# TCRT5000.net
KiCad netlist of a schematic drawn in Altium Designer
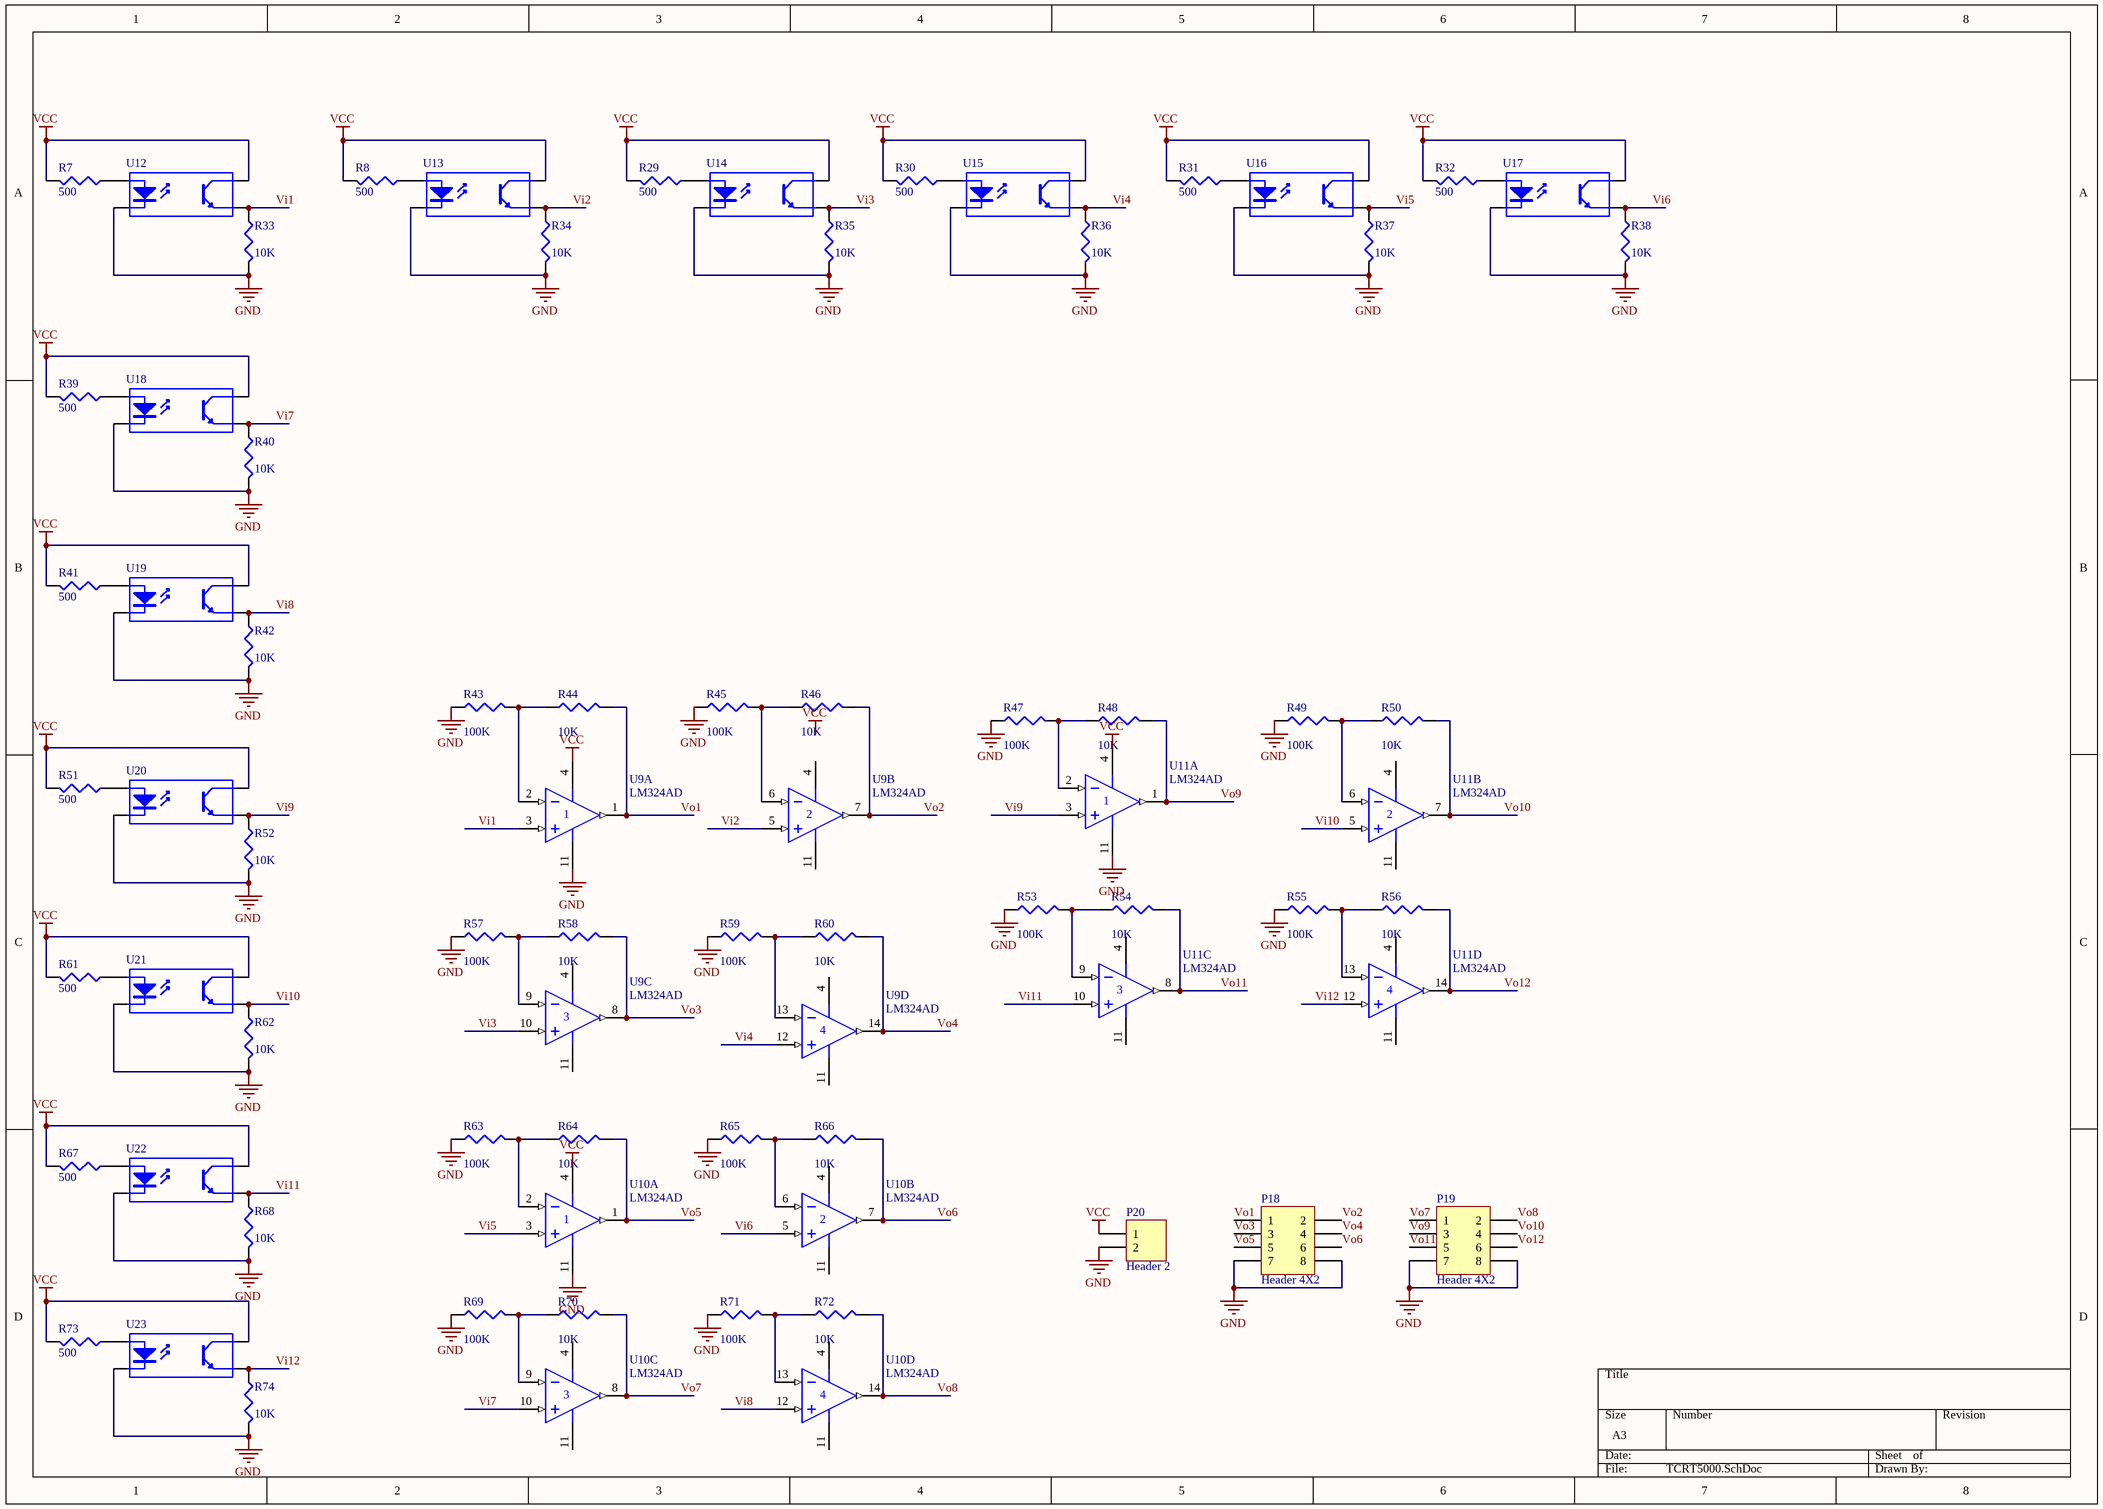
[diagram p0: TCRT5000.SchDoc]

(export (version "E")
  (design (tool "Eeschema 10.0.6"))
  (components
    (comp (ref "P18")
      (value "Header 4X2")
      (footprint "HDR2X4")
      (description "Header, 4-Pin, Dual row")
      (fields (field (name "PUBLISHER") "Altium Limited"))
      (libsource (lib "Miscellaneous Connectors") (part "Header 4X2"))
    )
    (comp (ref "P19")
      (value "Header 4X2")
      (footprint "HDR2X4")
      (description "Header, 4-Pin, Dual row")
      (fields (field (name "PUBLISHER") "Altium Limited"))
      (libsource (lib "Miscellaneous Connectors") (part "Header 4X2"))
    )
    (comp (ref "P20")
      (value "Header 2")
      (footprint "HDR1X2")
      (description "Header, 2-Pin")
      (fields (field (name "PUBLISHER") "Altium Limited"))
      (libsource (lib "Miscellaneous Connectors") (part "Header 2"))
    )
    (comp (ref "R7")
      (value "500")
      (description "Resistor")
      (fields (field (name "Comment") "Res3") (field (name "PUBLISHER") "Altium Limited"))
      (libsource (lib "Miscellaneous Devices") (part "Res3"))
    )
    (comp (ref "R8")
      (value "500")
      (description "Resistor")
      (fields (field (name "Comment") "Res3") (field (name "PUBLISHER") "Altium Limited"))
      (libsource (lib "Miscellaneous Devices") (part "Res3"))
    )
    (comp (ref "R29")
      (value "500")
      (description "Resistor")
      (fields (field (name "Comment") "Res3") (field (name "PUBLISHER") "Altium Limited"))
      (libsource (lib "Miscellaneous Devices") (part "Res3"))
    )
    (comp (ref "R30")
      (value "500")
      (description "Resistor")
      (fields (field (name "Comment") "Res3") (field (name "PUBLISHER") "Altium Limited"))
      (libsource (lib "Miscellaneous Devices") (part "Res3"))
    )
    (comp (ref "R31")
      (value "500")
      (description "Resistor")
      (fields (field (name "Comment") "Res3") (field (name "PUBLISHER") "Altium Limited"))
      (libsource (lib "Miscellaneous Devices") (part "Res3"))
    )
    (comp (ref "R32")
      (value "500")
      (description "Resistor")
      (fields (field (name "Comment") "Res3") (field (name "PUBLISHER") "Altium Limited"))
      (libsource (lib "Miscellaneous Devices") (part "Res3"))
    )
    (comp (ref "R33")
      (value "10K")
      (description "Resistor")
      (fields (field (name "Comment") "Res3") (field (name "PUBLISHER") "Altium Limited"))
      (libsource (lib "Miscellaneous Devices") (part "Res3"))
    )
    (comp (ref "R34")
      (value "10K")
      (description "Resistor")
      (fields (field (name "Comment") "Res3") (field (name "PUBLISHER") "Altium Limited"))
      (libsource (lib "Miscellaneous Devices") (part "Res3"))
    )
    (comp (ref "R35")
      (value "10K")
      (description "Resistor")
      (fields (field (name "Comment") "Res3") (field (name "PUBLISHER") "Altium Limited"))
      (libsource (lib "Miscellaneous Devices") (part "Res3"))
    )
    (comp (ref "R36")
      (value "10K")
      (description "Resistor")
      (fields (field (name "Comment") "Res3") (field (name "PUBLISHER") "Altium Limited"))
      (libsource (lib "Miscellaneous Devices") (part "Res3"))
    )
    (comp (ref "R37")
      (value "10K")
      (description "Resistor")
      (fields (field (name "Comment") "Res3") (field (name "PUBLISHER") "Altium Limited"))
      (libsource (lib "Miscellaneous Devices") (part "Res3"))
    )
    (comp (ref "R38")
      (value "10K")
      (description "Resistor")
      (fields (field (name "Comment") "Res3") (field (name "PUBLISHER") "Altium Limited"))
      (libsource (lib "Miscellaneous Devices") (part "Res3"))
    )
    (comp (ref "R39")
      (value "500")
      (description "Resistor")
      (fields (field (name "Comment") "Res3") (field (name "PUBLISHER") "Altium Limited"))
      (libsource (lib "Miscellaneous Devices") (part "Res3"))
    )
    (comp (ref "R40")
      (value "10K")
      (description "Resistor")
      (fields (field (name "Comment") "Res3") (field (name "PUBLISHER") "Altium Limited"))
      (libsource (lib "Miscellaneous Devices") (part "Res3"))
    )
    (comp (ref "R41")
      (value "500")
      (description "Resistor")
      (fields (field (name "Comment") "Res3") (field (name "PUBLISHER") "Altium Limited"))
      (libsource (lib "Miscellaneous Devices") (part "Res3"))
    )
    (comp (ref "R42")
      (value "10K")
      (description "Resistor")
      (fields (field (name "Comment") "Res3") (field (name "PUBLISHER") "Altium Limited"))
      (libsource (lib "Miscellaneous Devices") (part "Res3"))
    )
    (comp (ref "R43")
      (value "100K")
      (description "Resistor")
      (fields (field (name "Comment") "Res3") (field (name "PUBLISHER") "Altium Limited"))
      (libsource (lib "Miscellaneous Devices") (part "Res3"))
    )
    (comp (ref "R44")
      (value "10K")
      (description "Resistor")
      (fields (field (name "Comment") "Res3") (field (name "PUBLISHER") "Altium Limited"))
      (libsource (lib "Miscellaneous Devices") (part "Res3"))
    )
    (comp (ref "R45")
      (value "100K")
      (description "Resistor")
      (fields (field (name "Comment") "Res3") (field (name "PUBLISHER") "Altium Limited"))
      (libsource (lib "Miscellaneous Devices") (part "Res3"))
    )
    (comp (ref "R46")
      (value "10K")
      (description "Resistor")
      (fields (field (name "Comment") "Res3") (field (name "PUBLISHER") "Altium Limited"))
      (libsource (lib "Miscellaneous Devices") (part "Res3"))
    )
    (comp (ref "R47")
      (value "100K")
      (description "Resistor")
      (fields (field (name "Comment") "Res3") (field (name "PUBLISHER") "Altium Limited"))
      (libsource (lib "Miscellaneous Devices") (part "Res3"))
    )
    (comp (ref "R48")
      (value "10K")
      (description "Resistor")
      (fields (field (name "Comment") "Res3") (field (name "PUBLISHER") "Altium Limited"))
      (libsource (lib "Miscellaneous Devices") (part "Res3"))
    )
    (comp (ref "R49")
      (value "100K")
      (description "Resistor")
      (fields (field (name "Comment") "Res3") (field (name "PUBLISHER") "Altium Limited"))
      (libsource (lib "Miscellaneous Devices") (part "Res3"))
    )
    (comp (ref "R50")
      (value "10K")
      (description "Resistor")
      (fields (field (name "Comment") "Res3") (field (name "PUBLISHER") "Altium Limited"))
      (libsource (lib "Miscellaneous Devices") (part "Res3"))
    )
    (comp (ref "R51")
      (value "500")
      (description "Resistor")
      (fields (field (name "Comment") "Res3") (field (name "PUBLISHER") "Altium Limited"))
      (libsource (lib "Miscellaneous Devices") (part "Res3"))
    )
    (comp (ref "R52")
      (value "10K")
      (description "Resistor")
      (fields (field (name "Comment") "Res3") (field (name "PUBLISHER") "Altium Limited"))
      (libsource (lib "Miscellaneous Devices") (part "Res3"))
    )
    (comp (ref "R53")
      (value "100K")
      (description "Resistor")
      (fields (field (name "Comment") "Res3") (field (name "PUBLISHER") "Altium Limited"))
      (libsource (lib "Miscellaneous Devices") (part "Res3"))
    )
    (comp (ref "R54")
      (value "10K")
      (description "Resistor")
      (fields (field (name "Comment") "Res3") (field (name "PUBLISHER") "Altium Limited"))
      (libsource (lib "Miscellaneous Devices") (part "Res3"))
    )
    (comp (ref "R55")
      (value "100K")
      (description "Resistor")
      (fields (field (name "Comment") "Res3") (field (name "PUBLISHER") "Altium Limited"))
      (libsource (lib "Miscellaneous Devices") (part "Res3"))
    )
    (comp (ref "R56")
      (value "10K")
      (description "Resistor")
      (fields (field (name "Comment") "Res3") (field (name "PUBLISHER") "Altium Limited"))
      (libsource (lib "Miscellaneous Devices") (part "Res3"))
    )
    (comp (ref "R57")
      (value "100K")
      (description "Resistor")
      (fields (field (name "Comment") "Res3") (field (name "PUBLISHER") "Altium Limited"))
      (libsource (lib "Miscellaneous Devices") (part "Res3"))
    )
    (comp (ref "R58")
      (value "10K")
      (description "Resistor")
      (fields (field (name "Comment") "Res3") (field (name "PUBLISHER") "Altium Limited"))
      (libsource (lib "Miscellaneous Devices") (part "Res3"))
    )
    (comp (ref "R59")
      (value "100K")
      (description "Resistor")
      (fields (field (name "Comment") "Res3") (field (name "PUBLISHER") "Altium Limited"))
      (libsource (lib "Miscellaneous Devices") (part "Res3"))
    )
    (comp (ref "R60")
      (value "10K")
      (description "Resistor")
      (fields (field (name "Comment") "Res3") (field (name "PUBLISHER") "Altium Limited"))
      (libsource (lib "Miscellaneous Devices") (part "Res3"))
    )
    (comp (ref "R61")
      (value "500")
      (description "Resistor")
      (fields (field (name "Comment") "Res3") (field (name "PUBLISHER") "Altium Limited"))
      (libsource (lib "Miscellaneous Devices") (part "Res3"))
    )
    (comp (ref "R62")
      (value "10K")
      (description "Resistor")
      (fields (field (name "Comment") "Res3") (field (name "PUBLISHER") "Altium Limited"))
      (libsource (lib "Miscellaneous Devices") (part "Res3"))
    )
    (comp (ref "R63")
      (value "100K")
      (description "Resistor")
      (fields (field (name "Comment") "Res3") (field (name "PUBLISHER") "Altium Limited"))
      (libsource (lib "Miscellaneous Devices") (part "Res3"))
    )
    (comp (ref "R64")
      (value "10K")
      (description "Resistor")
      (fields (field (name "Comment") "Res3") (field (name "PUBLISHER") "Altium Limited"))
      (libsource (lib "Miscellaneous Devices") (part "Res3"))
    )
    (comp (ref "R65")
      (value "100K")
      (description "Resistor")
      (fields (field (name "Comment") "Res3") (field (name "PUBLISHER") "Altium Limited"))
      (libsource (lib "Miscellaneous Devices") (part "Res3"))
    )
    (comp (ref "R66")
      (value "10K")
      (description "Resistor")
      (fields (field (name "Comment") "Res3") (field (name "PUBLISHER") "Altium Limited"))
      (libsource (lib "Miscellaneous Devices") (part "Res3"))
    )
    (comp (ref "R67")
      (value "500")
      (description "Resistor")
      (fields (field (name "Comment") "Res3") (field (name "PUBLISHER") "Altium Limited"))
      (libsource (lib "Miscellaneous Devices") (part "Res3"))
    )
    (comp (ref "R68")
      (value "10K")
      (description "Resistor")
      (fields (field (name "Comment") "Res3") (field (name "PUBLISHER") "Altium Limited"))
      (libsource (lib "Miscellaneous Devices") (part "Res3"))
    )
    (comp (ref "R69")
      (value "100K")
      (description "Resistor")
      (fields (field (name "Comment") "Res3") (field (name "PUBLISHER") "Altium Limited"))
      (libsource (lib "Miscellaneous Devices") (part "Res3"))
    )
    (comp (ref "R70")
      (value "10K")
      (description "Resistor")
      (fields (field (name "Comment") "Res3") (field (name "PUBLISHER") "Altium Limited"))
      (libsource (lib "Miscellaneous Devices") (part "Res3"))
    )
    (comp (ref "R71")
      (value "100K")
      (description "Resistor")
      (fields (field (name "Comment") "Res3") (field (name "PUBLISHER") "Altium Limited"))
      (libsource (lib "Miscellaneous Devices") (part "Res3"))
    )
    (comp (ref "R72")
      (value "10K")
      (description "Resistor")
      (fields (field (name "Comment") "Res3") (field (name "PUBLISHER") "Altium Limited"))
      (libsource (lib "Miscellaneous Devices") (part "Res3"))
    )
    (comp (ref "R73")
      (value "500")
      (description "Resistor")
      (fields (field (name "Comment") "Res3") (field (name "PUBLISHER") "Altium Limited"))
      (libsource (lib "Miscellaneous Devices") (part "Res3"))
    )
    (comp (ref "R74")
      (value "10K")
      (description "Resistor")
      (fields (field (name "Comment") "Res3") (field (name "PUBLISHER") "Altium Limited"))
      (libsource (lib "Miscellaneous Devices") (part "Res3"))
    )
    (comp (ref "U9")
      (value "LM324AD")
      (footprint "D014_N")
      (description "Quadruple Operational Amplifier")
      (fields (field (name "PUBLISHER") "Altium Limited"))
      (libsource (lib "TI Operational Amplifier") (part "LM324AD"))
    )
    (comp (ref "U10")
      (value "LM324AD")
      (footprint "D014_N")
      (description "Quadruple Operational Amplifier")
      (fields (field (name "PUBLISHER") "Altium Limited"))
      (libsource (lib "TI Operational Amplifier") (part "LM324AD"))
    )
    (comp (ref "U11")
      (value "LM324AD")
      (footprint "D014_N")
      (description "Quadruple Operational Amplifier")
      (fields (field (name "PUBLISHER") "Altium Limited"))
      (libsource (lib "TI Operational Amplifier") (part "LM324AD"))
    )
    (comp (ref "U12")
      (value "Optoisolator1")
      (footprint "TCRT5000")
      (description "4-Pin Phototransistor Optocoupler")
      (fields (field (name "PUBLISHER") "Altium Limited"))
      (libsource (lib "Miscellaneous Devices") (part "Optoisolator1"))
    )
    (comp (ref "U13")
      (value "Optoisolator1")
      (footprint "TCRT5000")
      (description "4-Pin Phototransistor Optocoupler")
      (fields (field (name "PUBLISHER") "Altium Limited"))
      (libsource (lib "Miscellaneous Devices") (part "Optoisolator1"))
    )
    (comp (ref "U14")
      (value "Optoisolator1")
      (footprint "TCRT5000")
      (description "4-Pin Phototransistor Optocoupler")
      (fields (field (name "PUBLISHER") "Altium Limited"))
      (libsource (lib "Miscellaneous Devices") (part "Optoisolator1"))
    )
    (comp (ref "U15")
      (value "Optoisolator1")
      (footprint "TCRT5000")
      (description "4-Pin Phototransistor Optocoupler")
      (fields (field (name "PUBLISHER") "Altium Limited"))
      (libsource (lib "Miscellaneous Devices") (part "Optoisolator1"))
    )
    (comp (ref "U16")
      (value "Optoisolator1")
      (footprint "TCRT5000")
      (description "4-Pin Phototransistor Optocoupler")
      (fields (field (name "PUBLISHER") "Altium Limited"))
      (libsource (lib "Miscellaneous Devices") (part "Optoisolator1"))
    )
    (comp (ref "U17")
      (value "Optoisolator1")
      (footprint "TCRT5000")
      (description "4-Pin Phototransistor Optocoupler")
      (fields (field (name "PUBLISHER") "Altium Limited"))
      (libsource (lib "Miscellaneous Devices") (part "Optoisolator1"))
    )
    (comp (ref "U18")
      (value "Optoisolator1")
      (footprint "TCRT5000")
      (description "4-Pin Phototransistor Optocoupler")
      (fields (field (name "PUBLISHER") "Altium Limited"))
      (libsource (lib "Miscellaneous Devices") (part "Optoisolator1"))
    )
    (comp (ref "U19")
      (value "Optoisolator1")
      (footprint "TCRT5000")
      (description "4-Pin Phototransistor Optocoupler")
      (fields (field (name "PUBLISHER") "Altium Limited"))
      (libsource (lib "Miscellaneous Devices") (part "Optoisolator1"))
    )
    (comp (ref "U20")
      (value "Optoisolator1")
      (footprint "TCRT5000")
      (description "4-Pin Phototransistor Optocoupler")
      (fields (field (name "PUBLISHER") "Altium Limited"))
      (libsource (lib "Miscellaneous Devices") (part "Optoisolator1"))
    )
    (comp (ref "U21")
      (value "Optoisolator1")
      (footprint "TCRT5000")
      (description "4-Pin Phototransistor Optocoupler")
      (fields (field (name "PUBLISHER") "Altium Limited"))
      (libsource (lib "Miscellaneous Devices") (part "Optoisolator1"))
    )
    (comp (ref "U22")
      (value "Optoisolator1")
      (footprint "TCRT5000")
      (description "4-Pin Phototransistor Optocoupler")
      (fields (field (name "PUBLISHER") "Altium Limited"))
      (libsource (lib "Miscellaneous Devices") (part "Optoisolator1"))
    )
    (comp (ref "U23")
      (value "Optoisolator1")
      (footprint "TCRT5000")
      (description "4-Pin Phototransistor Optocoupler")
      (fields (field (name "PUBLISHER") "Altium Limited"))
      (libsource (lib "Miscellaneous Devices") (part "Optoisolator1"))
    )
  )
  (nets
    (net (code "1") (name "/Vi1") (class "Default")
      (node (ref "R33") (pin "1") (pinfunction "1_1") (pintype "passive"))
      (node (ref "U12") (pin "3") (pinfunction "E_3") (pintype "passive"))
      (node (ref "U9") (pin "3") (pinfunction "IN+_3") (pintype "input"))
    )
    (net (code "2") (name "/Vi2") (class "Default")
      (node (ref "R34") (pin "1") (pinfunction "1_1") (pintype "passive"))
      (node (ref "U13") (pin "3") (pinfunction "E_3") (pintype "passive"))
      (node (ref "U9") (pin "5") (pinfunction "IN+_5") (pintype "input"))
    )
    (net (code "3") (name "/Vi3") (class "Default")
      (node (ref "R35") (pin "1") (pinfunction "1_1") (pintype "passive"))
      (node (ref "U14") (pin "3") (pinfunction "E_3") (pintype "passive"))
      (node (ref "U9") (pin "10") (pinfunction "IN+_10") (pintype "input"))
    )
    (net (code "4") (name "/Vi4") (class "Default")
      (node (ref "R36") (pin "1") (pinfunction "1_1") (pintype "passive"))
      (node (ref "U15") (pin "3") (pinfunction "E_3") (pintype "passive"))
      (node (ref "U9") (pin "12") (pinfunction "IN+_12") (pintype "input"))
    )
    (net (code "5") (name "/Vi5") (class "Default")
      (node (ref "R37") (pin "1") (pinfunction "1_1") (pintype "passive"))
      (node (ref "U10") (pin "3") (pinfunction "IN+_3") (pintype "input"))
      (node (ref "U16") (pin "3") (pinfunction "E_3") (pintype "passive"))
    )
    (net (code "6") (name "/Vi6") (class "Default")
      (node (ref "R38") (pin "1") (pinfunction "1_1") (pintype "passive"))
      (node (ref "U10") (pin "5") (pinfunction "IN+_5") (pintype "input"))
      (node (ref "U17") (pin "3") (pinfunction "E_3") (pintype "passive"))
    )
    (net (code "7") (name "/Vi7") (class "Default")
      (node (ref "R40") (pin "1") (pinfunction "1_1") (pintype "passive"))
      (node (ref "U10") (pin "10") (pinfunction "IN+_10") (pintype "input"))
      (node (ref "U18") (pin "3") (pinfunction "E_3") (pintype "passive"))
    )
    (net (code "8") (name "/Vi8") (class "Default")
      (node (ref "R42") (pin "1") (pinfunction "1_1") (pintype "passive"))
      (node (ref "U10") (pin "12") (pinfunction "IN+_12") (pintype "input"))
      (node (ref "U19") (pin "3") (pinfunction "E_3") (pintype "passive"))
    )
    (net (code "9") (name "/Vi9") (class "Default")
      (node (ref "R52") (pin "1") (pinfunction "1_1") (pintype "passive"))
      (node (ref "U11") (pin "3") (pinfunction "IN+_3") (pintype "input"))
      (node (ref "U20") (pin "3") (pinfunction "E_3") (pintype "passive"))
    )
    (net (code "10") (name "/Vi10") (class "Default")
      (node (ref "R62") (pin "1") (pinfunction "1_1") (pintype "passive"))
      (node (ref "U11") (pin "5") (pinfunction "IN+_5") (pintype "input"))
      (node (ref "U21") (pin "3") (pinfunction "E_3") (pintype "passive"))
    )
    (net (code "11") (name "/Vi11") (class "Default")
      (node (ref "R68") (pin "1") (pinfunction "1_1") (pintype "passive"))
      (node (ref "U11") (pin "10") (pinfunction "IN+_10") (pintype "input"))
      (node (ref "U22") (pin "3") (pinfunction "E_3") (pintype "passive"))
    )
    (net (code "12") (name "/Vi12") (class "Default")
      (node (ref "R74") (pin "1") (pinfunction "1_1") (pintype "passive"))
      (node (ref "U11") (pin "12") (pinfunction "IN+_12") (pintype "input"))
      (node (ref "U23") (pin "3") (pinfunction "E_3") (pintype "passive"))
    )
    (net (code "13") (name "/Vo1") (class "Default")
      (node (ref "P18") (pin "1") (pinfunction "1_1") (pintype "passive"))
      (node (ref "R44") (pin "2") (pinfunction "2_2") (pintype "passive"))
      (node (ref "U9") (pin "1") (pinfunction "OUT_1") (pintype "output"))
    )
    (net (code "14") (name "/Vo2") (class "Default")
      (node (ref "P18") (pin "2") (pinfunction "2_2") (pintype "passive"))
      (node (ref "R46") (pin "2") (pinfunction "2_2") (pintype "passive"))
      (node (ref "U9") (pin "7") (pinfunction "OUT_7") (pintype "output"))
    )
    (net (code "15") (name "/Vo3") (class "Default")
      (node (ref "P18") (pin "3") (pinfunction "3_3") (pintype "passive"))
      (node (ref "R58") (pin "2") (pinfunction "2_2") (pintype "passive"))
      (node (ref "U9") (pin "8") (pinfunction "OUT_8") (pintype "output"))
    )
    (net (code "16") (name "/Vo4") (class "Default")
      (node (ref "P18") (pin "4") (pinfunction "4_4") (pintype "passive"))
      (node (ref "R60") (pin "2") (pinfunction "2_2") (pintype "passive"))
      (node (ref "U9") (pin "14") (pinfunction "OUT_14") (pintype "output"))
    )
    (net (code "17") (name "/Vo5") (class "Default")
      (node (ref "P18") (pin "5") (pinfunction "5_5") (pintype "passive"))
      (node (ref "R64") (pin "2") (pinfunction "2_2") (pintype "passive"))
      (node (ref "U10") (pin "1") (pinfunction "OUT_1") (pintype "output"))
    )
    (net (code "18") (name "/Vo6") (class "Default")
      (node (ref "P18") (pin "6") (pinfunction "6_6") (pintype "passive"))
      (node (ref "R66") (pin "2") (pinfunction "2_2") (pintype "passive"))
      (node (ref "U10") (pin "7") (pinfunction "OUT_7") (pintype "output"))
    )
    (net (code "19") (name "/Vo7") (class "Default")
      (node (ref "P19") (pin "1") (pinfunction "1_1") (pintype "passive"))
      (node (ref "R70") (pin "2") (pinfunction "2_2") (pintype "passive"))
      (node (ref "U10") (pin "8") (pinfunction "OUT_8") (pintype "output"))
    )
    (net (code "20") (name "/Vo8") (class "Default")
      (node (ref "P19") (pin "2") (pinfunction "2_2") (pintype "passive"))
      (node (ref "R72") (pin "2") (pinfunction "2_2") (pintype "passive"))
      (node (ref "U10") (pin "14") (pinfunction "OUT_14") (pintype "output"))
    )
    (net (code "21") (name "/Vo9") (class "Default")
      (node (ref "P19") (pin "3") (pinfunction "3_3") (pintype "passive"))
      (node (ref "R48") (pin "2") (pinfunction "2_2") (pintype "passive"))
      (node (ref "U11") (pin "1") (pinfunction "OUT_1") (pintype "output"))
    )
    (net (code "22") (name "/Vo10") (class "Default")
      (node (ref "P19") (pin "4") (pinfunction "4_4") (pintype "passive"))
      (node (ref "R50") (pin "2") (pinfunction "2_2") (pintype "passive"))
      (node (ref "U11") (pin "7") (pinfunction "OUT_7") (pintype "output"))
    )
    (net (code "23") (name "/Vo11") (class "Default")
      (node (ref "P19") (pin "5") (pinfunction "5_5") (pintype "passive"))
      (node (ref "R54") (pin "2") (pinfunction "2_2") (pintype "passive"))
      (node (ref "U11") (pin "8") (pinfunction "OUT_8") (pintype "output"))
    )
    (net (code "24") (name "/Vo12") (class "Default")
      (node (ref "P19") (pin "6") (pinfunction "6_6") (pintype "passive"))
      (node (ref "R56") (pin "2") (pinfunction "2_2") (pintype "passive"))
      (node (ref "U11") (pin "14") (pinfunction "OUT_14") (pintype "output"))
    )
    (net (code "25") (name "GND") (class "Default")
      (node (ref "P18") (pin "7") (pinfunction "7_7") (pintype "passive"))
      (node (ref "P18") (pin "8") (pinfunction "8_8") (pintype "passive"))
      (node (ref "P19") (pin "7") (pinfunction "7_7") (pintype "passive"))
      (node (ref "P19") (pin "8") (pinfunction "8_8") (pintype "passive"))
      (node (ref "P20") (pin "2") (pinfunction "2_2") (pintype "passive"))
      (node (ref "R33") (pin "2") (pinfunction "2_2") (pintype "passive"))
      (node (ref "R34") (pin "2") (pinfunction "2_2") (pintype "passive"))
      (node (ref "R35") (pin "2") (pinfunction "2_2") (pintype "passive"))
      (node (ref "R36") (pin "2") (pinfunction "2_2") (pintype "passive"))
      (node (ref "R37") (pin "2") (pinfunction "2_2") (pintype "passive"))
      (node (ref "R38") (pin "2") (pinfunction "2_2") (pintype "passive"))
      (node (ref "R40") (pin "2") (pinfunction "2_2") (pintype "passive"))
      (node (ref "R42") (pin "2") (pinfunction "2_2") (pintype "passive"))
      (node (ref "R43") (pin "1") (pinfunction "1_1") (pintype "passive"))
      (node (ref "R45") (pin "1") (pinfunction "1_1") (pintype "passive"))
      (node (ref "R47") (pin "1") (pinfunction "1_1") (pintype "passive"))
      (node (ref "R49") (pin "1") (pinfunction "1_1") (pintype "passive"))
      (node (ref "R52") (pin "2") (pinfunction "2_2") (pintype "passive"))
      (node (ref "R53") (pin "1") (pinfunction "1_1") (pintype "passive"))
      (node (ref "R55") (pin "1") (pinfunction "1_1") (pintype "passive"))
      (node (ref "R57") (pin "1") (pinfunction "1_1") (pintype "passive"))
      (node (ref "R59") (pin "1") (pinfunction "1_1") (pintype "passive"))
      (node (ref "R62") (pin "2") (pinfunction "2_2") (pintype "passive"))
      (node (ref "R63") (pin "1") (pinfunction "1_1") (pintype "passive"))
      (node (ref "R65") (pin "1") (pinfunction "1_1") (pintype "passive"))
      (node (ref "R68") (pin "2") (pinfunction "2_2") (pintype "passive"))
      (node (ref "R69") (pin "1") (pinfunction "1_1") (pintype "passive"))
      (node (ref "R71") (pin "1") (pinfunction "1_1") (pintype "passive"))
      (node (ref "R74") (pin "2") (pinfunction "2_2") (pintype "passive"))
      (node (ref "U10") (pin "11") (pinfunction "V-_11") (pintype "power_in"))
      (node (ref "U11") (pin "11") (pinfunction "V-_11") (pintype "power_in"))
      (node (ref "U12") (pin "2") (pinfunction "K_2") (pintype "passive"))
      (node (ref "U13") (pin "2") (pinfunction "K_2") (pintype "passive"))
      (node (ref "U14") (pin "2") (pinfunction "K_2") (pintype "passive"))
      (node (ref "U15") (pin "2") (pinfunction "K_2") (pintype "passive"))
      (node (ref "U16") (pin "2") (pinfunction "K_2") (pintype "passive"))
      (node (ref "U17") (pin "2") (pinfunction "K_2") (pintype "passive"))
      (node (ref "U18") (pin "2") (pinfunction "K_2") (pintype "passive"))
      (node (ref "U19") (pin "2") (pinfunction "K_2") (pintype "passive"))
      (node (ref "U20") (pin "2") (pinfunction "K_2") (pintype "passive"))
      (node (ref "U21") (pin "2") (pinfunction "K_2") (pintype "passive"))
      (node (ref "U22") (pin "2") (pinfunction "K_2") (pintype "passive"))
      (node (ref "U23") (pin "2") (pinfunction "K_2") (pintype "passive"))
      (node (ref "U9") (pin "11") (pinfunction "V-_11") (pintype "power_in"))
    )
    (net (code "26") (name "Net-(U9A-IN-)") (class "Default")
      (node (ref "R43") (pin "2") (pinfunction "2_2") (pintype "passive"))
      (node (ref "R44") (pin "1") (pinfunction "1_1") (pintype "passive"))
      (node (ref "U9") (pin "2") (pinfunction "IN-_2") (pintype "input"))
    )
    (net (code "27") (name "Net-(U9B-IN-)") (class "Default")
      (node (ref "R45") (pin "2") (pinfunction "2_2") (pintype "passive"))
      (node (ref "R46") (pin "1") (pinfunction "1_1") (pintype "passive"))
      (node (ref "U9") (pin "6") (pinfunction "IN-_6") (pintype "input"))
    )
    (net (code "28") (name "Net-(U9C-IN-)") (class "Default")
      (node (ref "R57") (pin "2") (pinfunction "2_2") (pintype "passive"))
      (node (ref "R58") (pin "1") (pinfunction "1_1") (pintype "passive"))
      (node (ref "U9") (pin "9") (pinfunction "IN-_9") (pintype "input"))
    )
    (net (code "29") (name "Net-(U9D-IN-)") (class "Default")
      (node (ref "R59") (pin "2") (pinfunction "2_2") (pintype "passive"))
      (node (ref "R60") (pin "1") (pinfunction "1_1") (pintype "passive"))
      (node (ref "U9") (pin "13") (pinfunction "IN-_13") (pintype "input"))
    )
    (net (code "30") (name "Net-(U10A-IN-)") (class "Default")
      (node (ref "R63") (pin "2") (pinfunction "2_2") (pintype "passive"))
      (node (ref "R64") (pin "1") (pinfunction "1_1") (pintype "passive"))
      (node (ref "U10") (pin "2") (pinfunction "IN-_2") (pintype "input"))
    )
    (net (code "31") (name "Net-(U10B-IN-)") (class "Default")
      (node (ref "R65") (pin "2") (pinfunction "2_2") (pintype "passive"))
      (node (ref "R66") (pin "1") (pinfunction "1_1") (pintype "passive"))
      (node (ref "U10") (pin "6") (pinfunction "IN-_6") (pintype "input"))
    )
    (net (code "32") (name "Net-(U10C-IN-)") (class "Default")
      (node (ref "R69") (pin "2") (pinfunction "2_2") (pintype "passive"))
      (node (ref "R70") (pin "1") (pinfunction "1_1") (pintype "passive"))
      (node (ref "U10") (pin "9") (pinfunction "IN-_9") (pintype "input"))
    )
    (net (code "33") (name "Net-(U10D-IN-)") (class "Default")
      (node (ref "R71") (pin "2") (pinfunction "2_2") (pintype "passive"))
      (node (ref "R72") (pin "1") (pinfunction "1_1") (pintype "passive"))
      (node (ref "U10") (pin "13") (pinfunction "IN-_13") (pintype "input"))
    )
    (net (code "34") (name "Net-(U11A-IN-)") (class "Default")
      (node (ref "R47") (pin "2") (pinfunction "2_2") (pintype "passive"))
      (node (ref "R48") (pin "1") (pinfunction "1_1") (pintype "passive"))
      (node (ref "U11") (pin "2") (pinfunction "IN-_2") (pintype "input"))
    )
    (net (code "35") (name "Net-(U11B-IN-)") (class "Default")
      (node (ref "R49") (pin "2") (pinfunction "2_2") (pintype "passive"))
      (node (ref "R50") (pin "1") (pinfunction "1_1") (pintype "passive"))
      (node (ref "U11") (pin "6") (pinfunction "IN-_6") (pintype "input"))
    )
    (net (code "36") (name "Net-(U11C-IN-)") (class "Default")
      (node (ref "R53") (pin "2") (pinfunction "2_2") (pintype "passive"))
      (node (ref "R54") (pin "1") (pinfunction "1_1") (pintype "passive"))
      (node (ref "U11") (pin "9") (pinfunction "IN-_9") (pintype "input"))
    )
    (net (code "37") (name "Net-(U11D-IN-)") (class "Default")
      (node (ref "R55") (pin "2") (pinfunction "2_2") (pintype "passive"))
      (node (ref "R56") (pin "1") (pinfunction "1_1") (pintype "passive"))
      (node (ref "U11") (pin "13") (pinfunction "IN-_13") (pintype "input"))
    )
    (net (code "38") (name "Net-(U12-A)") (class "Default")
      (node (ref "R7") (pin "1") (pinfunction "1_1") (pintype "passive"))
      (node (ref "U12") (pin "1") (pinfunction "A_1") (pintype "passive"))
    )
    (net (code "39") (name "Net-(U13-A)") (class "Default")
      (node (ref "R8") (pin "1") (pinfunction "1_1") (pintype "passive"))
      (node (ref "U13") (pin "1") (pinfunction "A_1") (pintype "passive"))
    )
    (net (code "40") (name "Net-(U14-A)") (class "Default")
      (node (ref "R29") (pin "1") (pinfunction "1_1") (pintype "passive"))
      (node (ref "U14") (pin "1") (pinfunction "A_1") (pintype "passive"))
    )
    (net (code "41") (name "Net-(U15-A)") (class "Default")
      (node (ref "R30") (pin "1") (pinfunction "1_1") (pintype "passive"))
      (node (ref "U15") (pin "1") (pinfunction "A_1") (pintype "passive"))
    )
    (net (code "42") (name "Net-(U16-A)") (class "Default")
      (node (ref "R31") (pin "1") (pinfunction "1_1") (pintype "passive"))
      (node (ref "U16") (pin "1") (pinfunction "A_1") (pintype "passive"))
    )
    (net (code "43") (name "Net-(U17-A)") (class "Default")
      (node (ref "R32") (pin "1") (pinfunction "1_1") (pintype "passive"))
      (node (ref "U17") (pin "1") (pinfunction "A_1") (pintype "passive"))
    )
    (net (code "44") (name "Net-(U18-A)") (class "Default")
      (node (ref "R39") (pin "1") (pinfunction "1_1") (pintype "passive"))
      (node (ref "U18") (pin "1") (pinfunction "A_1") (pintype "passive"))
    )
    (net (code "45") (name "Net-(U19-A)") (class "Default")
      (node (ref "R41") (pin "1") (pinfunction "1_1") (pintype "passive"))
      (node (ref "U19") (pin "1") (pinfunction "A_1") (pintype "passive"))
    )
    (net (code "46") (name "Net-(U20-A)") (class "Default")
      (node (ref "R51") (pin "1") (pinfunction "1_1") (pintype "passive"))
      (node (ref "U20") (pin "1") (pinfunction "A_1") (pintype "passive"))
    )
    (net (code "47") (name "Net-(U21-A)") (class "Default")
      (node (ref "R61") (pin "1") (pinfunction "1_1") (pintype "passive"))
      (node (ref "U21") (pin "1") (pinfunction "A_1") (pintype "passive"))
    )
    (net (code "48") (name "Net-(U22-A)") (class "Default")
      (node (ref "R67") (pin "1") (pinfunction "1_1") (pintype "passive"))
      (node (ref "U22") (pin "1") (pinfunction "A_1") (pintype "passive"))
    )
    (net (code "49") (name "Net-(U23-A)") (class "Default")
      (node (ref "R73") (pin "1") (pinfunction "1_1") (pintype "passive"))
      (node (ref "U23") (pin "1") (pinfunction "A_1") (pintype "passive"))
    )
    (net (code "50") (name "VCC") (class "Default")
      (node (ref "P20") (pin "1") (pinfunction "1_1") (pintype "passive"))
      (node (ref "R29") (pin "2") (pinfunction "2_2") (pintype "passive"))
      (node (ref "R30") (pin "2") (pinfunction "2_2") (pintype "passive"))
      (node (ref "R31") (pin "2") (pinfunction "2_2") (pintype "passive"))
      (node (ref "R32") (pin "2") (pinfunction "2_2") (pintype "passive"))
      (node (ref "R39") (pin "2") (pinfunction "2_2") (pintype "passive"))
      (node (ref "R41") (pin "2") (pinfunction "2_2") (pintype "passive"))
      (node (ref "R51") (pin "2") (pinfunction "2_2") (pintype "passive"))
      (node (ref "R61") (pin "2") (pinfunction "2_2") (pintype "passive"))
      (node (ref "R67") (pin "2") (pinfunction "2_2") (pintype "passive"))
      (node (ref "R7") (pin "2") (pinfunction "2_2") (pintype "passive"))
      (node (ref "R73") (pin "2") (pinfunction "2_2") (pintype "passive"))
      (node (ref "R8") (pin "2") (pinfunction "2_2") (pintype "passive"))
      (node (ref "U10") (pin "4") (pinfunction "V+_4") (pintype "power_in"))
      (node (ref "U11") (pin "4") (pinfunction "V+_4") (pintype "power_in"))
      (node (ref "U12") (pin "4") (pinfunction "C_4") (pintype "passive"))
      (node (ref "U13") (pin "4") (pinfunction "C_4") (pintype "passive"))
      (node (ref "U14") (pin "4") (pinfunction "C_4") (pintype "passive"))
      (node (ref "U15") (pin "4") (pinfunction "C_4") (pintype "passive"))
      (node (ref "U16") (pin "4") (pinfunction "C_4") (pintype "passive"))
      (node (ref "U17") (pin "4") (pinfunction "C_4") (pintype "passive"))
      (node (ref "U18") (pin "4") (pinfunction "C_4") (pintype "passive"))
      (node (ref "U19") (pin "4") (pinfunction "C_4") (pintype "passive"))
      (node (ref "U20") (pin "4") (pinfunction "C_4") (pintype "passive"))
      (node (ref "U21") (pin "4") (pinfunction "C_4") (pintype "passive"))
      (node (ref "U22") (pin "4") (pinfunction "C_4") (pintype "passive"))
      (node (ref "U23") (pin "4") (pinfunction "C_4") (pintype "passive"))
      (node (ref "U9") (pin "4") (pinfunction "V+_4") (pintype "power_in"))
    )
    (net (code "51") (name "unconnected-(U9B-V+-Pad4)") (class "Default")
      (node (ref "U9") (pin "4") (pinfunction "V+_4") (pintype "power_in"))
    )
    (net (code "52") (name "unconnected-(U9B-V--Pad11)") (class "Default")
      (node (ref "U9") (pin "11") (pinfunction "V-_11") (pintype "power_in"))
    )
    (net (code "53") (name "unconnected-(U9C-V+-Pad4)") (class "Default")
      (node (ref "U9") (pin "4") (pinfunction "V+_4") (pintype "power_in"))
    )
    (net (code "54") (name "unconnected-(U9C-V--Pad11)") (class "Default")
      (node (ref "U9") (pin "11") (pinfunction "V-_11") (pintype "power_in"))
    )
    (net (code "55") (name "unconnected-(U9D-V+-Pad4)") (class "Default")
      (node (ref "U9") (pin "4") (pinfunction "V+_4") (pintype "power_in"))
    )
    (net (code "56") (name "unconnected-(U9D-V--Pad11)") (class "Default")
      (node (ref "U9") (pin "11") (pinfunction "V-_11") (pintype "power_in"))
    )
    (net (code "57") (name "unconnected-(U10B-V+-Pad4)") (class "Default")
      (node (ref "U10") (pin "4") (pinfunction "V+_4") (pintype "power_in"))
    )
    (net (code "58") (name "unconnected-(U10B-V--Pad11)") (class "Default")
      (node (ref "U10") (pin "11") (pinfunction "V-_11") (pintype "power_in"))
    )
    (net (code "59") (name "unconnected-(U10C-V+-Pad4)") (class "Default")
      (node (ref "U10") (pin "4") (pinfunction "V+_4") (pintype "power_in"))
    )
    (net (code "60") (name "unconnected-(U10C-V--Pad11)") (class "Default")
      (node (ref "U10") (pin "11") (pinfunction "V-_11") (pintype "power_in"))
    )
    (net (code "61") (name "unconnected-(U10D-V+-Pad4)") (class "Default")
      (node (ref "U10") (pin "4") (pinfunction "V+_4") (pintype "power_in"))
    )
    (net (code "62") (name "unconnected-(U10D-V--Pad11)") (class "Default")
      (node (ref "U10") (pin "11") (pinfunction "V-_11") (pintype "power_in"))
    )
    (net (code "63") (name "unconnected-(U11B-V+-Pad4)") (class "Default")
      (node (ref "U11") (pin "4") (pinfunction "V+_4") (pintype "power_in"))
    )
    (net (code "64") (name "unconnected-(U11B-V--Pad11)") (class "Default")
      (node (ref "U11") (pin "11") (pinfunction "V-_11") (pintype "power_in"))
    )
    (net (code "65") (name "unconnected-(U11C-V+-Pad4)") (class "Default")
      (node (ref "U11") (pin "4") (pinfunction "V+_4") (pintype "power_in"))
    )
    (net (code "66") (name "unconnected-(U11C-V--Pad11)") (class "Default")
      (node (ref "U11") (pin "11") (pinfunction "V-_11") (pintype "power_in"))
    )
    (net (code "67") (name "unconnected-(U11D-V+-Pad4)") (class "Default")
      (node (ref "U11") (pin "4") (pinfunction "V+_4") (pintype "power_in"))
    )
    (net (code "68") (name "unconnected-(U11D-V--Pad11)") (class "Default")
      (node (ref "U11") (pin "11") (pinfunction "V-_11") (pintype "power_in"))
    )
  )
)
